# CAP1203.net
KiCad netlist of a schematic drawn in EAGLE
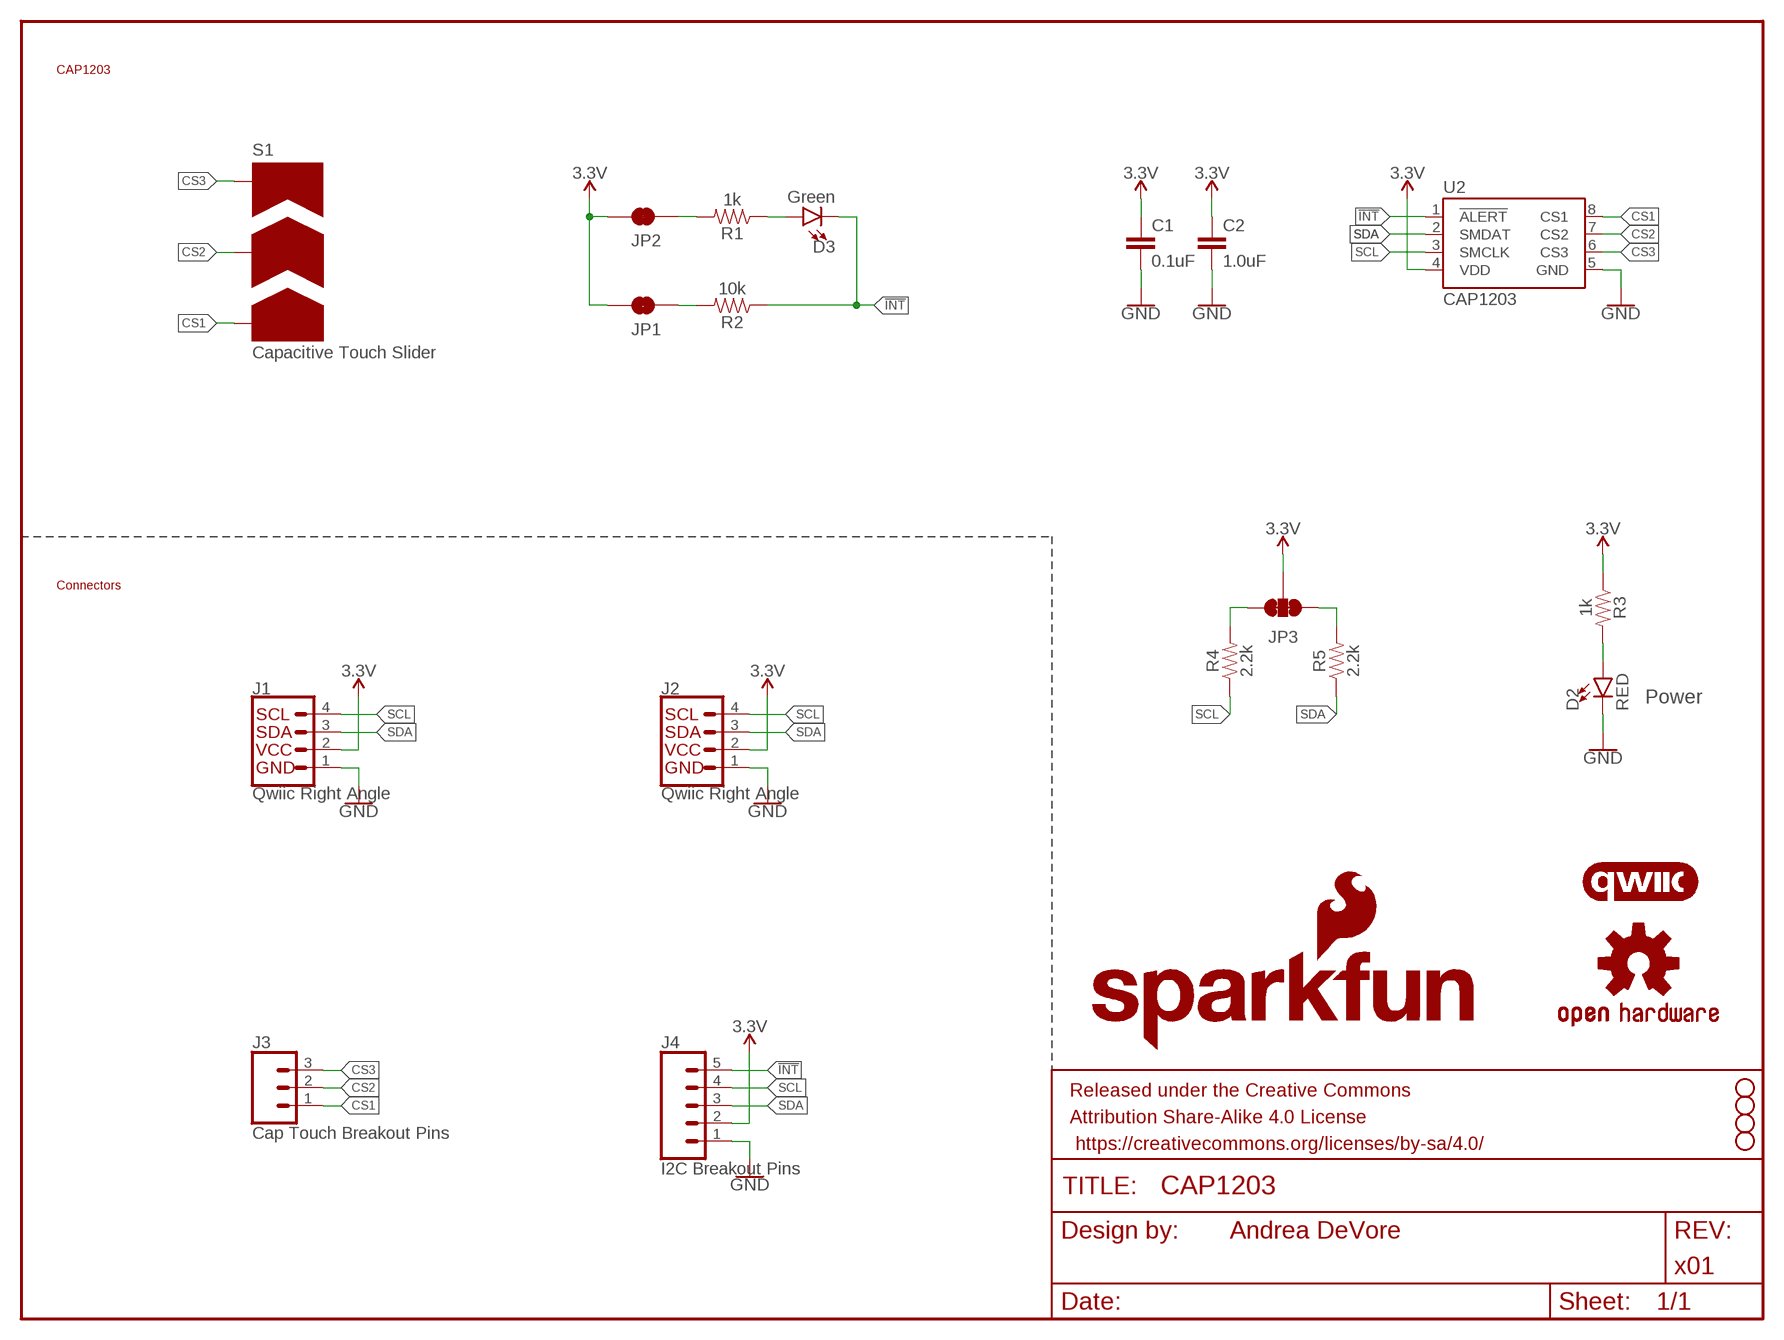
[diagram p0: schematic, sheet 1]

(export (version "E")
  (design (tool "Eeschema 10.0.6"))
  (components
    (comp (ref "C1")
      (value "0.1uF")
      (footprint "eagle-import:0603")
      (libsource (lib "eagle-import") (part "0.1UF-0603-25V-5%"))
    )
    (comp (ref "C2")
      (value "1.0uF")
      (footprint "eagle-import:0603")
      (libsource (lib "eagle-import") (part "1.0UF-0603-16V-10%"))
    )
    (comp (ref "D2")
      (value "RED")
      (footprint "eagle-import:LED-0603")
      (libsource (lib "eagle-import") (part "LED-RED0603"))
    )
    (comp (ref "D3")
      (value "Green")
      (footprint "eagle-import:LED-1206-BOTTOM")
      (libsource (lib "eagle-import") (part "LED-GREEN1206-BOTTOM"))
    )
    (comp (ref "FRAME1")
      (value "FRAME-LETTER")
      (footprint "eagle-import:CREATIVE_COMMONS")
      (libsource (lib "eagle-import") (part "FRAME-LETTER"))
    )
    (comp (ref "H1")
      (value "STAND-OFF")
      (footprint "eagle-import:STAND-OFF")
      (libsource (lib "eagle-import") (part "STAND-OFF"))
    )
    (comp (ref "H2")
      (value "STAND-OFF")
      (footprint "eagle-import:STAND-OFF")
      (libsource (lib "eagle-import") (part "STAND-OFF"))
    )
    (comp (ref "H3")
      (value "STAND-OFF")
      (footprint "eagle-import:STAND-OFF")
      (libsource (lib "eagle-import") (part "STAND-OFF"))
    )
    (comp (ref "H5")
      (value "STAND-OFF")
      (footprint "eagle-import:STAND-OFF")
      (libsource (lib "eagle-import") (part "STAND-OFF"))
    )
    (comp (ref "J1")
      (value "Qwiic Right Angle")
      (footprint "eagle-import:JST04_1MM_RA")
      (libsource (lib "eagle-import") (part "I2C_STANDARDQWIIC"))
    )
    (comp (ref "J2")
      (value "Qwiic Right Angle")
      (footprint "eagle-import:JST04_1MM_RA")
      (libsource (lib "eagle-import") (part "I2C_STANDARDQWIIC"))
    )
    (comp (ref "J3")
      (value "Cap Touch Breakout Pins")
      (footprint "eagle-import:1X03_NO_SILK")
      (libsource (lib "eagle-import") (part "CONN_031X03_NO_SILK"))
    )
    (comp (ref "J4")
      (value "I2C Breakout Pins")
      (footprint "eagle-import:1X05_NO_SILK")
      (libsource (lib "eagle-import") (part "CONN_05NO_SILK"))
    )
    (comp (ref "JP1")
      (value "JUMPER-SMT_2_NC_TRACE_SILK")
      (footprint "eagle-import:SMT-JUMPER_2_NC_TRACE_SILK")
      (libsource (lib "eagle-import") (part "JUMPER-SMT_2_NC_TRACE_SILK"))
    )
    (comp (ref "JP2")
      (value "JUMPER-SMT_2_NC_TRACE_SILK")
      (footprint "eagle-import:SMT-JUMPER_2_NC_TRACE_SILK")
      (libsource (lib "eagle-import") (part "JUMPER-SMT_2_NC_TRACE_SILK"))
    )
    (comp (ref "JP3")
      (value "JUMPER-SMT_3_2-NC_TRACE_SILK")
      (footprint "eagle-import:SMT-JUMPER_3_2-NC_TRACE_SILK")
      (libsource (lib "eagle-import") (part "JUMPER-SMT_3_2-NC_TRACE_SILK"))
    )
    (comp (ref "LOGO1")
      (value "SFE_LOGO_NAME_FLAME.1_INCH")
      (footprint "eagle-import:SFE_LOGO_NAME_FLAME_.1")
      (libsource (lib "eagle-import") (part "SFE_LOGO_NAME_FLAME.1_INCH"))
    )
    (comp (ref "LOGO3")
      (value "OSHW-LOGOS")
      (footprint "eagle-import:OSHW-LOGO-S")
      (libsource (lib "eagle-import") (part "OSHW-LOGOS"))
    )
    (comp (ref "R1")
      (value "1k")
      (footprint "eagle-import:0603")
      (libsource (lib "eagle-import") (part "1KOHM-0603-1/10W-1%"))
    )
    (comp (ref "R2")
      (value "10k")
      (footprint "eagle-import:0603")
      (libsource (lib "eagle-import") (part "10KOHM-0603-1/10W-1%"))
    )
    (comp (ref "R3")
      (value "1k")
      (footprint "eagle-import:0603")
      (libsource (lib "eagle-import") (part "1KOHM-0603-1/10W-1%"))
    )
    (comp (ref "R4")
      (value "2.2k")
      (footprint "eagle-import:0603")
      (libsource (lib "eagle-import") (part "2.2KOHM-0603-1/10W-1%"))
    )
    (comp (ref "R5")
      (value "2.2k")
      (footprint "eagle-import:0603")
      (libsource (lib "eagle-import") (part "2.2KOHM-0603-1/10W-1%"))
    )
    (comp (ref "S1")
      (value "CAP_SENSE_SLIDER")
      (footprint "eagle-import:CAP_SENSE_SLIDER")
      (libsource (lib "eagle-import") (part "CAP_SENSE_SLIDER"))
    )
    (comp (ref "U$17")
      (value "QWIIC_LOGO_5MM")
      (footprint "eagle-import:QWIIC_5MM")
      (libsource (lib "eagle-import") (part "QWIIC_LOGO_5MM"))
    )
    (comp (ref "U2")
      (value "CAP1203")
      (footprint "eagle-import:SO08-TIGHT")
      (libsource (lib "eagle-import") (part "CAP1203"))
    )
  )
  (nets
    (net (code "1") (name "/~{INT}") (class "Default")
      (node (ref "D3") (pin "C") (pinfunction "C_C") (pintype "passive"))
      (node (ref "J4") (pin "5") (pinfunction "5_5") (pintype "passive"))
      (node (ref "R2") (pin "1") (pinfunction "1_1") (pintype "passive"))
      (node (ref "U2") (pin "1") (pinfunction "~{ALERT}_1") (pintype "output"))
    )
    (net (code "2") (name "3.3V") (class "Default")
      (node (ref "C1") (pin "1") (pinfunction "1_1") (pintype "passive"))
      (node (ref "C2") (pin "1") (pinfunction "1_1") (pintype "passive"))
      (node (ref "J1") (pin "2") (pinfunction "2_2") (pintype "power_in"))
      (node (ref "J2") (pin "2") (pinfunction "2_2") (pintype "power_in"))
      (node (ref "J4") (pin "2") (pinfunction "2_2") (pintype "passive"))
      (node (ref "JP1") (pin "2") (pinfunction "2_2") (pintype "passive"))
      (node (ref "JP2") (pin "2") (pinfunction "2_2") (pintype "passive"))
      (node (ref "JP3") (pin "2") (pinfunction "2_2") (pintype "passive"))
      (node (ref "R3") (pin "1") (pinfunction "1_1") (pintype "passive"))
      (node (ref "U2") (pin "4") (pinfunction "VDD_4") (pintype "power_in"))
    )
    (net (code "3") (name "CS1") (class "Default")
      (node (ref "J3") (pin "1") (pinfunction "1_1") (pintype "passive"))
      (node (ref "S1") (pin "1") (pinfunction "1_1") (pintype "bidirectional"))
      (node (ref "U2") (pin "8") (pinfunction "CS1_8") (pintype "bidirectional"))
    )
    (net (code "4") (name "CS2") (class "Default")
      (node (ref "J3") (pin "2") (pinfunction "2_2") (pintype "passive"))
      (node (ref "S1") (pin "2") (pinfunction "2_2") (pintype "bidirectional"))
      (node (ref "U2") (pin "7") (pinfunction "CS2_7") (pintype "bidirectional"))
    )
    (net (code "5") (name "CS3") (class "Default")
      (node (ref "J3") (pin "3") (pinfunction "3_3") (pintype "passive"))
      (node (ref "S1") (pin "3") (pinfunction "3_3") (pintype "bidirectional"))
      (node (ref "U2") (pin "6") (pinfunction "CS3_6") (pintype "bidirectional"))
    )
    (net (code "6") (name "GND") (class "Default")
      (node (ref "C1") (pin "2") (pinfunction "2_2") (pintype "passive"))
      (node (ref "C2") (pin "2") (pinfunction "2_2") (pintype "passive"))
      (node (ref "D2") (pin "C") (pinfunction "C_C") (pintype "passive"))
      (node (ref "J1") (pin "1") (pinfunction "1_1") (pintype "power_in"))
      (node (ref "J2") (pin "1") (pinfunction "1_1") (pintype "power_in"))
      (node (ref "J4") (pin "1") (pinfunction "1_1") (pintype "passive"))
      (node (ref "U2") (pin "5") (pinfunction "GND_5") (pintype "power_in"))
    )
    (net (code "7") (name "Net-(D2-PadA)") (class "Default")
      (node (ref "D2") (pin "A") (pinfunction "A_A") (pintype "passive"))
      (node (ref "R3") (pin "2") (pinfunction "2_2") (pintype "passive"))
    )
    (net (code "8") (name "Net-(D3-PadA)") (class "Default")
      (node (ref "D3") (pin "A") (pinfunction "A_A") (pintype "passive"))
      (node (ref "R1") (pin "1") (pinfunction "1_1") (pintype "passive"))
    )
    (net (code "9") (name "Net-(JP1-Pad1)") (class "Default")
      (node (ref "JP1") (pin "1") (pinfunction "1_1") (pintype "passive"))
      (node (ref "R2") (pin "2") (pinfunction "2_2") (pintype "passive"))
    )
    (net (code "10") (name "Net-(JP2-Pad1)") (class "Default")
      (node (ref "JP2") (pin "1") (pinfunction "1_1") (pintype "passive"))
      (node (ref "R1") (pin "2") (pinfunction "2_2") (pintype "passive"))
    )
    (net (code "11") (name "Net-(JP3-Pad1)") (class "Default")
      (node (ref "JP3") (pin "1") (pinfunction "1_1") (pintype "passive"))
      (node (ref "R5") (pin "2") (pinfunction "2_2") (pintype "passive"))
    )
    (net (code "12") (name "Net-(JP3-Pad3)") (class "Default")
      (node (ref "JP3") (pin "3") (pinfunction "3_3") (pintype "passive"))
      (node (ref "R4") (pin "2") (pinfunction "2_2") (pintype "passive"))
    )
    (net (code "13") (name "SCL") (class "Default")
      (node (ref "J1") (pin "4") (pinfunction "4_4") (pintype "passive"))
      (node (ref "J2") (pin "4") (pinfunction "4_4") (pintype "passive"))
      (node (ref "J4") (pin "4") (pinfunction "4_4") (pintype "passive"))
      (node (ref "R4") (pin "1") (pinfunction "1_1") (pintype "passive"))
      (node (ref "U2") (pin "3") (pinfunction "SMCLK_3") (pintype "input"))
    )
    (net (code "14") (name "SDA") (class "Default")
      (node (ref "J1") (pin "3") (pinfunction "3_3") (pintype "passive"))
      (node (ref "J2") (pin "3") (pinfunction "3_3") (pintype "passive"))
      (node (ref "J4") (pin "3") (pinfunction "3_3") (pintype "passive"))
      (node (ref "R5") (pin "1") (pinfunction "1_1") (pintype "passive"))
      (node (ref "U2") (pin "2") (pinfunction "SMDAT_2") (pintype "bidirectional"))
    )
  )
)
